# g3528-plcc2-led-breakout.net
KiCad netlist of a schematic drawn in EAGLE
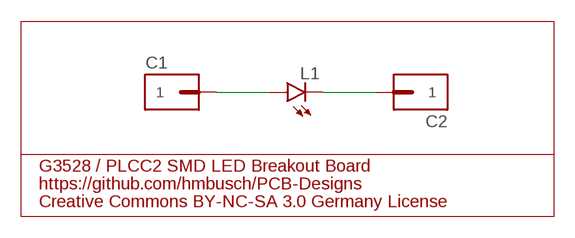
[diagram p0: schematic, sheet 1]

(export (version "E")
  (design (tool "Eeschema 10.0.6"))
  (components
    (comp (ref "C1")
      (value "PIN_HEADER_1-WIDE")
      (footprint "eagle-import:BREAKAWAY_STRAIGHT_1_WIDE")
      (libsource (lib "eagle-import") (part "PIN_HEADER_1-WIDE"))
    )
    (comp (ref "C2")
      (value "PIN_HEADER_1-WIDE")
      (footprint "eagle-import:BREAKAWAY_STRAIGHT_1_WIDE")
      (libsource (lib "eagle-import") (part "PIN_HEADER_1-WIDE"))
    )
    (comp (ref "L1")
      (value "LED-G3528")
      (footprint "eagle-import:G3528")
      (libsource (lib "eagle-import") (part "LED-G3528"))
    )
  )
  (nets
    (net (code "1") (name "Net-(L1-ANODE)") (class "Default")
      (node (ref "C1") (pin "1") (pinfunction "1_1") (pintype "bidirectional"))
      (node (ref "L1") (pin "A") (pinfunction "ANODE_A") (pintype "passive"))
    )
    (net (code "2") (name "Net-(L1-CATHODE)") (class "Default")
      (node (ref "C2") (pin "1") (pinfunction "1_1") (pintype "bidirectional"))
      (node (ref "L1") (pin "C") (pinfunction "CATHODE_C") (pintype "passive"))
    )
  )
)
